# power_supply.net
KiCad netlist of a schematic drawn in Altium Designer
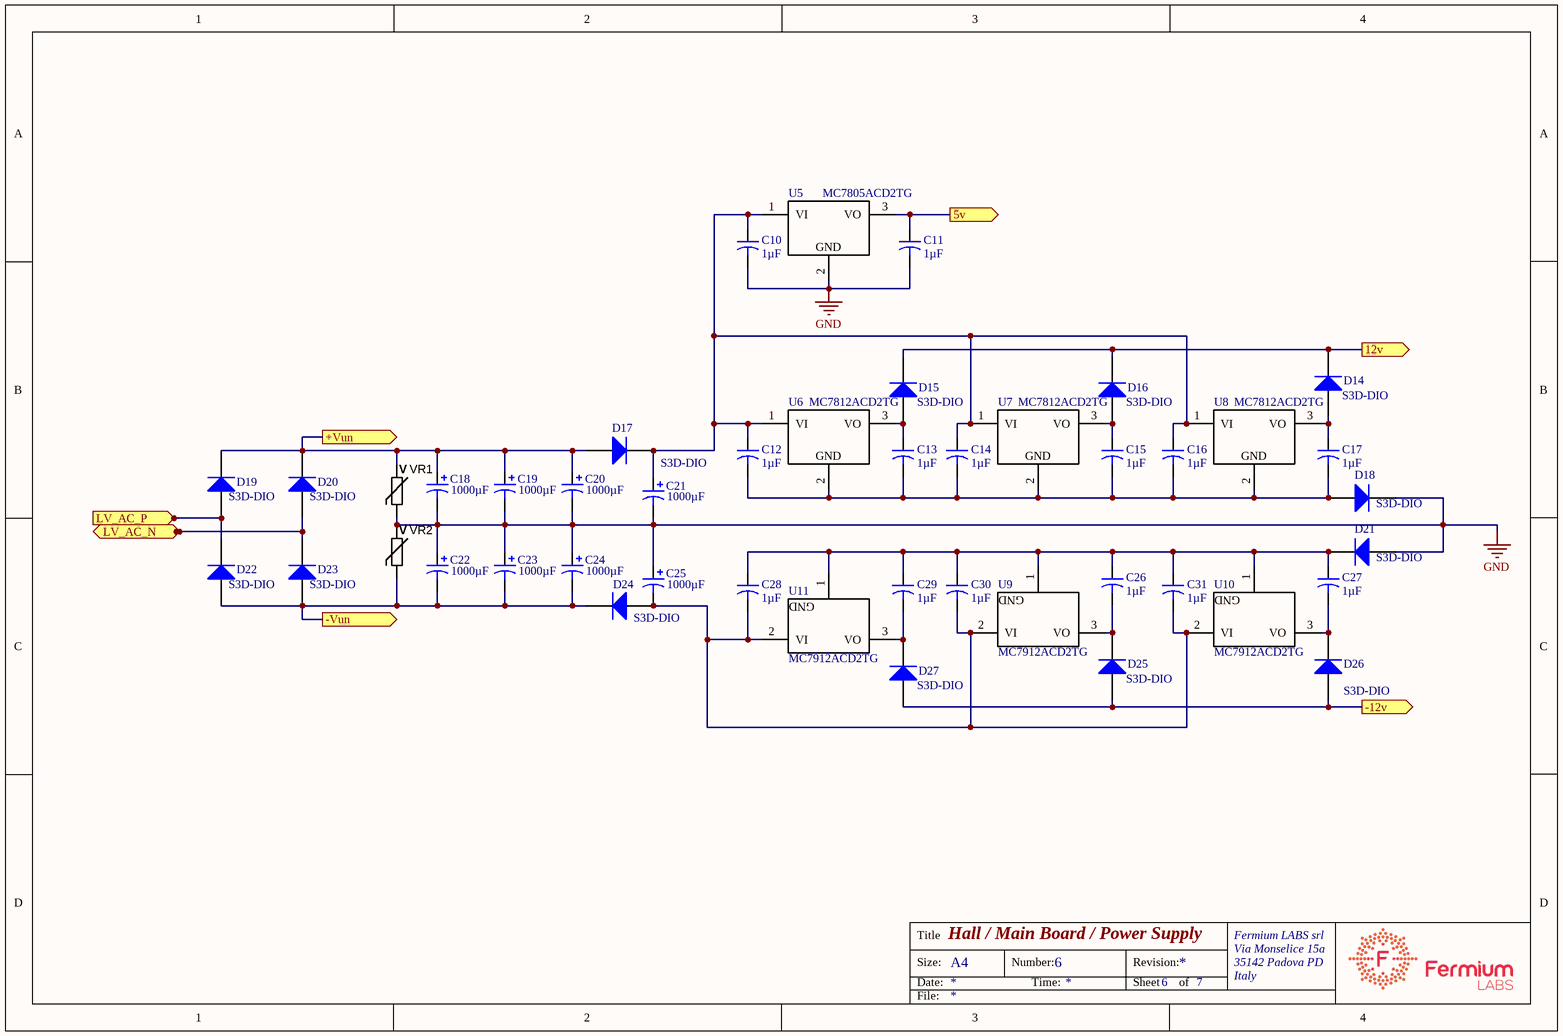
[diagram p0: power_supply.SchDoc]

(export (version "E")
  (design (tool "Eeschema 10.0.6"))
  (components
    (comp (ref "C10")
      (value "~")
      (footprint "Passives:CAP 0805/2012")
      (description "Capacitor")
      (fields
        (field (name "MANUFACTURER") "SAMSUNG")
        (field (name "MANUFACTURER PART NUMBER") "CL21B105KAFNNNE")
        (field (name "CAPACITANCE") "1µF")
        (field (name "PUBLISHER") "Altium Limited")
      )
      (libsource (lib "Miscellaneous Devices") (part "Cap2"))
    )
    (comp (ref "C11")
      (value "~")
      (footprint "Passives:CAP 0805/2012")
      (description "Capacitor")
      (fields
        (field (name "MANUFACTURER") "SAMSUNG")
        (field (name "MANUFACTURER PART NUMBER") "CL21B105KAFNNNE")
        (field (name "CAPACITANCE") "1µF")
        (field (name "PUBLISHER") "Altium Limited")
      )
      (libsource (lib "Miscellaneous Devices") (part "Cap2"))
    )
    (comp (ref "C12")
      (value "~")
      (footprint "Passives:CAP 0805/2012")
      (description "Capacitor")
      (fields
        (field (name "MANUFACTURER") "SAMSUNG")
        (field (name "MANUFACTURER PART NUMBER") "CL21B105KAFNNNE")
        (field (name "CAPACITANCE") "1µF")
        (field (name "PUBLISHER") "Altium Limited")
      )
      (libsource (lib "Miscellaneous Devices") (part "Cap2"))
    )
    (comp (ref "C13")
      (value "~")
      (footprint "Passives:CAP 0805/2012")
      (description "Capacitor")
      (fields
        (field (name "MANUFACTURER") "SAMSUNG")
        (field (name "MANUFACTURER PART NUMBER") "CL21B105KAFNNNE")
        (field (name "CAPACITANCE") "1µF")
        (field (name "PUBLISHER") "Altium Limited")
      )
      (libsource (lib "Miscellaneous Devices") (part "Cap2"))
    )
    (comp (ref "C14")
      (value "~")
      (footprint "Passives:CAP 0805/2012")
      (description "Capacitor")
      (fields
        (field (name "MANUFACTURER") "SAMSUNG")
        (field (name "MANUFACTURER PART NUMBER") "CL21B105KAFNNNE")
        (field (name "CAPACITANCE") "1µF")
        (field (name "PUBLISHER") "Altium Limited")
      )
      (libsource (lib "Miscellaneous Devices") (part "Cap2"))
    )
    (comp (ref "C15")
      (value "~")
      (footprint "Passives:CAP 0805/2012")
      (description "Capacitor")
      (fields
        (field (name "MANUFACTURER") "SAMSUNG")
        (field (name "MANUFACTURER PART NUMBER") "CL21B105KAFNNNE")
        (field (name "CAPACITANCE") "1µF")
        (field (name "PUBLISHER") "Altium Limited")
      )
      (libsource (lib "Miscellaneous Devices") (part "Cap2"))
    )
    (comp (ref "C16")
      (value "~")
      (footprint "Passives:CAP 0805/2012")
      (description "Capacitor")
      (fields
        (field (name "MANUFACTURER") "SAMSUNG")
        (field (name "MANUFACTURER PART NUMBER") "CL21B105KAFNNNE")
        (field (name "CAPACITANCE") "1µF")
        (field (name "PUBLISHER") "Altium Limited")
      )
      (libsource (lib "Miscellaneous Devices") (part "Cap2"))
    )
    (comp (ref "C17")
      (value "~")
      (footprint "Passives:CAP 0805/2012")
      (description "Capacitor")
      (fields
        (field (name "MANUFACTURER") "SAMSUNG")
        (field (name "MANUFACTURER PART NUMBER") "CL21B105KAFNNNE")
        (field (name "CAPACITANCE") "1µF")
        (field (name "PUBLISHER") "Altium Limited")
      )
      (libsource (lib "Miscellaneous Devices") (part "Cap2"))
    )
    (comp (ref "C18")
      (value "~")
      (footprint "PBL - THD Packages:CAPE5.0mm")
      (description "capacitor , electrolytic")
      (fields
        (field (name "MANUFACTURER") "NICHICON")
        (field (name "MANUFACTURER PART NUMBER") "UVZ1V102MHD")
        (field (name "CAPACITANCE") "1000µF")
        (field (name "PUBLISHER") "Altium Limited")
      )
      (libsource (lib "Miscellaneous Devices") (part "Cap Pol1"))
    )
    (comp (ref "C19")
      (value "~")
      (footprint "PBL - THD Packages:CAPE5.0mm")
      (description "capacitor , electrolytic")
      (fields
        (field (name "MANUFACTURER") "NICHICON")
        (field (name "MANUFACTURER PART NUMBER") "UVZ1V102MHD")
        (field (name "CAPACITANCE") "1000µF")
        (field (name "PUBLISHER") "Altium Limited")
      )
      (libsource (lib "Miscellaneous Devices") (part "Cap Pol1"))
    )
    (comp (ref "C20")
      (value "~")
      (footprint "PBL - THD Packages:CAPE5.0mm")
      (description "capacitor , electrolytic")
      (fields
        (field (name "MANUFACTURER") "NICHICON")
        (field (name "MANUFACTURER PART NUMBER") "UVZ1V102MHD")
        (field (name "CAPACITANCE") "1000µF")
        (field (name "PUBLISHER") "Altium Limited")
      )
      (libsource (lib "Miscellaneous Devices") (part "Cap Pol1"))
    )
    (comp (ref "C21")
      (value "~")
      (footprint "PBL - THD Packages:CAPE5.0mm")
      (description "capacitor , electrolytic")
      (fields
        (field (name "MANUFACTURER") "NICHICON")
        (field (name "MANUFACTURER PART NUMBER") "UVZ1V102MHD")
        (field (name "CAPACITANCE") "1000µF")
        (field (name "PUBLISHER") "Altium Limited")
      )
      (libsource (lib "Miscellaneous Devices") (part "Cap Pol1"))
    )
    (comp (ref "C22")
      (value "~")
      (footprint "PBL - THD Packages:CAPE5.0mm")
      (description "capacitor , electrolytic")
      (fields
        (field (name "MANUFACTURER") "NICHICON")
        (field (name "MANUFACTURER PART NUMBER") "UVZ1V102MHD")
        (field (name "CAPACITANCE") "1000µF")
        (field (name "PUBLISHER") "Altium Limited")
      )
      (libsource (lib "Miscellaneous Devices") (part "Cap Pol1"))
    )
    (comp (ref "C23")
      (value "~")
      (footprint "PBL - THD Packages:CAPE5.0mm")
      (description "capacitor , electrolytic")
      (fields
        (field (name "MANUFACTURER") "NICHICON")
        (field (name "MANUFACTURER PART NUMBER") "UVZ1V102MHD")
        (field (name "CAPACITANCE") "1000µF")
        (field (name "PUBLISHER") "Altium Limited")
      )
      (libsource (lib "Miscellaneous Devices") (part "Cap Pol1"))
    )
    (comp (ref "C24")
      (value "~")
      (footprint "PBL - THD Packages:CAPE5.0mm")
      (description "capacitor , electrolytic")
      (fields
        (field (name "MANUFACTURER") "NICHICON")
        (field (name "MANUFACTURER PART NUMBER") "UVZ1V102MHD")
        (field (name "CAPACITANCE") "1000µF")
        (field (name "PUBLISHER") "Altium Limited")
      )
      (libsource (lib "Miscellaneous Devices") (part "Cap Pol1"))
    )
    (comp (ref "C25")
      (value "~")
      (footprint "PBL - THD Packages:CAPE5.0mm")
      (description "capacitor , electrolytic")
      (fields
        (field (name "MANUFACTURER") "NICHICON")
        (field (name "MANUFACTURER PART NUMBER") "UVZ1V102MHD")
        (field (name "CAPACITANCE") "1000µF")
        (field (name "PUBLISHER") "Altium Limited")
      )
      (libsource (lib "Miscellaneous Devices") (part "Cap Pol1"))
    )
    (comp (ref "C26")
      (value "~")
      (footprint "Passives:CAP 0805/2012")
      (description "Capacitor")
      (fields
        (field (name "MANUFACTURER") "SAMSUNG")
        (field (name "MANUFACTURER PART NUMBER") "CL21B105KAFNNNE")
        (field (name "CAPACITANCE") "1µF")
        (field (name "PUBLISHER") "Altium Limited")
      )
      (libsource (lib "Miscellaneous Devices") (part "Cap2"))
    )
    (comp (ref "C27")
      (value "~")
      (footprint "Passives:CAP 0805/2012")
      (description "Capacitor")
      (fields
        (field (name "MANUFACTURER") "SAMSUNG")
        (field (name "MANUFACTURER PART NUMBER") "CL21B105KAFNNNE")
        (field (name "CAPACITANCE") "1µF")
        (field (name "PUBLISHER") "Altium Limited")
      )
      (libsource (lib "Miscellaneous Devices") (part "Cap2"))
    )
    (comp (ref "C28")
      (value "~")
      (footprint "Passives:CAP 0805/2012")
      (description "Capacitor")
      (fields
        (field (name "MANUFACTURER") "SAMSUNG")
        (field (name "MANUFACTURER PART NUMBER") "CL21B105KAFNNNE")
        (field (name "CAPACITANCE") "1µF")
        (field (name "PUBLISHER") "Altium Limited")
      )
      (libsource (lib "Miscellaneous Devices") (part "Cap2"))
    )
    (comp (ref "C29")
      (value "~")
      (footprint "Passives:CAP 0805/2012")
      (description "Capacitor")
      (fields
        (field (name "MANUFACTURER") "SAMSUNG")
        (field (name "MANUFACTURER PART NUMBER") "CL21B105KAFNNNE")
        (field (name "CAPACITANCE") "1µF")
        (field (name "PUBLISHER") "Altium Limited")
      )
      (libsource (lib "Miscellaneous Devices") (part "Cap2"))
    )
    (comp (ref "C30")
      (value "~")
      (footprint "Passives:CAP 0805/2012")
      (description "Capacitor")
      (fields
        (field (name "MANUFACTURER") "SAMSUNG")
        (field (name "MANUFACTURER PART NUMBER") "CL21B105KAFNNNE")
        (field (name "CAPACITANCE") "1µF")
        (field (name "PUBLISHER") "Altium Limited")
      )
      (libsource (lib "Miscellaneous Devices") (part "Cap2"))
    )
    (comp (ref "C31")
      (value "~")
      (footprint "Passives:CAP 0805/2012")
      (description "Capacitor")
      (fields
        (field (name "MANUFACTURER") "SAMSUNG")
        (field (name "MANUFACTURER PART NUMBER") "CL21B105KAFNNNE")
        (field (name "CAPACITANCE") "1µF")
        (field (name "PUBLISHER") "Altium Limited")
      )
      (libsource (lib "Miscellaneous Devices") (part "Cap2"))
    )
    (comp (ref "D14")
      (value "~")
      (footprint "DIODE-SMC")
      (description "Diode rectifier 1A")
      (fields
        (field (name "SUPPLIER PART NUMBER 1") "S3D-DIO")
        (field (name "MANUFACTURER") "DIOTEC SEMICONDUCTOR")
        (field (name "MANUFACTURER PART NUMBER") "S3D")
      )
      (libsource (lib "Miscellaneous Devices") (part "Diode 1N4007"))
    )
    (comp (ref "D15")
      (value "~")
      (footprint "DIODE-SMC")
      (description "Diode rectifier 1A")
      (fields
        (field (name "SUPPLIER PART NUMBER 1") "S3D-DIO")
        (field (name "MANUFACTURER") "DIOTEC SEMICONDUCTOR")
        (field (name "MANUFACTURER PART NUMBER") "S3D")
      )
      (libsource (lib "Miscellaneous Devices") (part "Diode 1N4007"))
    )
    (comp (ref "D16")
      (value "~")
      (footprint "DIODE-SMC")
      (description "Diode rectifier 1A")
      (fields
        (field (name "SUPPLIER PART NUMBER 1") "S3D-DIO")
        (field (name "MANUFACTURER") "DIOTEC SEMICONDUCTOR")
        (field (name "MANUFACTURER PART NUMBER") "S3D")
      )
      (libsource (lib "Miscellaneous Devices") (part "Diode 1N4007"))
    )
    (comp (ref "D17")
      (value "~")
      (footprint "DIODE-SMC")
      (description "Diode rectifier 1A")
      (fields
        (field (name "SUPPLIER PART NUMBER 1") "S3D-DIO")
        (field (name "MANUFACTURER") "DIOTEC SEMICONDUCTOR")
        (field (name "MANUFACTURER PART NUMBER") "S3D")
      )
      (libsource (lib "Miscellaneous Devices") (part "Diode 1N4007"))
    )
    (comp (ref "D18")
      (value "~")
      (footprint "DIODE-SMC")
      (description "Diode rectifier 1A")
      (fields
        (field (name "SUPPLIER PART NUMBER 1") "S3D-DIO")
        (field (name "MANUFACTURER") "DIOTEC SEMICONDUCTOR")
        (field (name "MANUFACTURER PART NUMBER") "S3D")
      )
      (libsource (lib "Miscellaneous Devices") (part "Diode 1N4007"))
    )
    (comp (ref "D19")
      (value "~")
      (footprint "DIODE-SMC")
      (description "Diode rectifier 1A")
      (fields
        (field (name "SUPPLIER PART NUMBER 1") "S3D-DIO")
        (field (name "MANUFACTURER") "DIOTEC SEMICONDUCTOR")
        (field (name "MANUFACTURER PART NUMBER") "S3D")
      )
      (libsource (lib "Miscellaneous Devices") (part "Diode 1N4007"))
    )
    (comp (ref "D20")
      (value "~")
      (footprint "DIODE-SMC")
      (description "Diode rectifier 1A")
      (fields
        (field (name "SUPPLIER PART NUMBER 1") "S3D-DIO")
        (field (name "MANUFACTURER") "DIOTEC SEMICONDUCTOR")
        (field (name "MANUFACTURER PART NUMBER") "S3D")
      )
      (libsource (lib "Miscellaneous Devices") (part "Diode 1N4007"))
    )
    (comp (ref "D21")
      (value "~")
      (footprint "DIODE-SMC")
      (description "Diode rectifier 1A")
      (fields
        (field (name "SUPPLIER PART NUMBER 1") "S3D-DIO")
        (field (name "MANUFACTURER") "DIOTEC SEMICONDUCTOR")
        (field (name "MANUFACTURER PART NUMBER") "S3D")
      )
      (libsource (lib "Miscellaneous Devices") (part "Diode 1N4007"))
    )
    (comp (ref "D22")
      (value "~")
      (footprint "DIODE-SMC")
      (description "Diode rectifier 1A")
      (fields
        (field (name "SUPPLIER PART NUMBER 1") "S3D-DIO")
        (field (name "MANUFACTURER") "DIOTEC SEMICONDUCTOR")
        (field (name "MANUFACTURER PART NUMBER") "S3D")
      )
      (libsource (lib "Miscellaneous Devices") (part "Diode 1N4007"))
    )
    (comp (ref "D23")
      (value "~")
      (footprint "DIODE-SMC")
      (description "Diode rectifier 1A")
      (fields
        (field (name "SUPPLIER PART NUMBER 1") "S3D-DIO")
        (field (name "MANUFACTURER") "DIOTEC SEMICONDUCTOR")
        (field (name "MANUFACTURER PART NUMBER") "S3D")
      )
      (libsource (lib "Miscellaneous Devices") (part "Diode 1N4007"))
    )
    (comp (ref "D24")
      (value "~")
      (footprint "DIODE-SMC")
      (description "Diode rectifier 1A")
      (fields
        (field (name "SUPPLIER PART NUMBER 1") "S3D-DIO")
        (field (name "MANUFACTURER") "DIOTEC SEMICONDUCTOR")
        (field (name "MANUFACTURER PART NUMBER") "S3D")
      )
      (libsource (lib "Miscellaneous Devices") (part "Diode 1N4007"))
    )
    (comp (ref "D25")
      (value "~")
      (footprint "DIODE-SMC")
      (description "Diode rectifier 1A")
      (fields
        (field (name "SUPPLIER PART NUMBER 1") "S3D-DIO")
        (field (name "MANUFACTURER") "DIOTEC SEMICONDUCTOR")
        (field (name "MANUFACTURER PART NUMBER") "S3D")
      )
      (libsource (lib "Miscellaneous Devices") (part "Diode 1N4007"))
    )
    (comp (ref "D26")
      (value "~")
      (footprint "DIODE-SMC")
      (description "Diode rectifier 1A")
      (fields
        (field (name "SUPPLIER PART NUMBER 1") "S3D-DIO")
        (field (name "MANUFACTURER") "DIOTEC SEMICONDUCTOR")
        (field (name "MANUFACTURER PART NUMBER") "S3D")
      )
      (libsource (lib "Miscellaneous Devices") (part "Diode 1N4007"))
    )
    (comp (ref "D27")
      (value "~")
      (footprint "DIODE-SMC")
      (description "Diode rectifier 1A")
      (fields
        (field (name "SUPPLIER PART NUMBER 1") "S3D-DIO")
        (field (name "MANUFACTURER") "DIOTEC SEMICONDUCTOR")
        (field (name "MANUFACTURER PART NUMBER") "S3D")
      )
      (libsource (lib "Miscellaneous Devices") (part "Diode 1N4007"))
    )
    (comp (ref "U5")
      (value "~")
      (footprint "PBL - SMD Packages:D2PAK-3")
      (description "Voltage regulator, 5V")
      (fields
        (field (name "SUPPLIER PART NUMBER 1") "MC7805ACD2TG")
        (field (name "MANUFACTURER") "ON SEMICONDUCTOR")
        (field (name "MANUFACTURER PART NUMBER") "MC7805ACD2TG")
      )
      (libsource (lib "vh_altium_library") (part "L7805-TO220"))
    )
    (comp (ref "U6")
      (value "~")
      (footprint "PBL - SMD Packages:D2PAK-3")
      (description "Voltage regulator, 15V")
      (fields
        (field (name "SUPPLIER PART NUMBER 1") "MC7812ACD2TG")
        (field (name "MANUFACTURER") "ON SEMICONDUCTOR")
        (field (name "MANUFACTURER PART NUMBER") "MC7812ACD2TG")
      )
      (libsource (lib "vh_altium_library") (part "L7815-TO220"))
    )
    (comp (ref "U7")
      (value "~")
      (footprint "PBL - SMD Packages:D2PAK-3")
      (description "Voltage regulator, 15V")
      (fields
        (field (name "SUPPLIER PART NUMBER 1") "MC7812ACD2TG")
        (field (name "MANUFACTURER") "ON SEMICONDUCTOR")
        (field (name "MANUFACTURER PART NUMBER") "MC7812ACD2TG")
      )
      (libsource (lib "vh_altium_library") (part "L7815-TO220"))
    )
    (comp (ref "U8")
      (value "~")
      (footprint "PBL - SMD Packages:D2PAK-3")
      (description "Voltage regulator, 15V")
      (fields
        (field (name "SUPPLIER PART NUMBER 1") "MC7812ACD2TG")
        (field (name "MANUFACTURER") "ON SEMICONDUCTOR")
        (field (name "MANUFACTURER PART NUMBER") "MC7812ACD2TG")
      )
      (libsource (lib "vh_altium_library") (part "L7815-TO220"))
    )
    (comp (ref "U9")
      (value "~")
      (footprint "PBL - SMD Packages:D2PAK-3")
      (description "Voltage regulator-15.0V")
      (fields
        (field (name "SUPPLIER PART NUMBER 1") "MC7912ACD2TG")
        (field (name "MANUFACTURER") "ON SEMICONDUCTOR")
        (field (name "MANUFACTURER PART NUMBER") "MC7912ACD2TG")
      )
      (libsource (lib "vh_altium_library") (part "L7915-TO220"))
    )
    (comp (ref "U10")
      (value "~")
      (footprint "PBL - SMD Packages:D2PAK-3")
      (description "Voltage regulator-15.0V")
      (fields
        (field (name "SUPPLIER PART NUMBER 1") "MC7912ACD2TG")
        (field (name "MANUFACTURER") "ON SEMICONDUCTOR")
        (field (name "MANUFACTURER PART NUMBER") "MC7912ACD2TG")
      )
      (libsource (lib "vh_altium_library") (part "L7915-TO220"))
    )
    (comp (ref "U11")
      (value "~")
      (footprint "PBL - SMD Packages:D2PAK-3")
      (description "Voltage regulator-15.0V")
      (fields
        (field (name "SUPPLIER PART NUMBER 1") "MC7912ACD2TG")
        (field (name "MANUFACTURER") "ON SEMICONDUCTOR")
        (field (name "MANUFACTURER PART NUMBER") "MC7912ACD2TG")
      )
      (libsource (lib "vh_altium_library") (part "L7915-TO220"))
    )
    (comp (ref "VR1")
      (value "~")
      (footprint "CAP 1206/3216 - 1.8MM")
      (description "Varistor")
      (fields
        (field (name "MANUFACTURER") "EPCOS")
        (field (name "MANUFACTURER PART NUMBER") "B72520T0250K062")
      )
      (libsource (lib "PBL - Fuses and Protection") (part "Varistor_MOV"))
    )
    (comp (ref "VR2")
      (value "~")
      (footprint "CAP 1206/3216 - 1.8MM")
      (description "Varistor")
      (fields
        (field (name "MANUFACTURER") "EPCOS")
        (field (name "MANUFACTURER PART NUMBER") "B72520T0250K062")
      )
      (libsource (lib "PBL - Fuses and Protection") (part "Varistor_MOV"))
    )
  )
  (nets
    (net (code "1") (name "/+Vun") (class "Default")
      (node (ref "C18") (pin "1") (pinfunction "1_1") (pintype "passive"))
      (node (ref "C19") (pin "1") (pinfunction "1_1") (pintype "passive"))
      (node (ref "C20") (pin "1") (pinfunction "1_1") (pintype "passive"))
      (node (ref "D17") (pin "A") (pinfunction "A_A") (pintype "passive"))
      (node (ref "D19") (pin "K") (pinfunction "K_K") (pintype "passive"))
      (node (ref "D20") (pin "K") (pinfunction "K_K") (pintype "passive"))
      (node (ref "VR1") (pin "1") (pinfunction "1_1") (pintype "passive"))
    )
    (net (code "2") (name "/-12v") (class "Default")
      (node (ref "D25") (pin "A") (pinfunction "A_A") (pintype "passive"))
      (node (ref "D26") (pin "A") (pinfunction "A_A") (pintype "passive"))
      (node (ref "D27") (pin "A") (pinfunction "A_A") (pintype "passive"))
    )
    (net (code "3") (name "/-Vun") (class "Default")
      (node (ref "C22") (pin "2") (pinfunction "2_2") (pintype "passive"))
      (node (ref "C23") (pin "2") (pinfunction "2_2") (pintype "passive"))
      (node (ref "C24") (pin "2") (pinfunction "2_2") (pintype "passive"))
      (node (ref "D22") (pin "A") (pinfunction "A_A") (pintype "passive"))
      (node (ref "D23") (pin "A") (pinfunction "A_A") (pintype "passive"))
      (node (ref "D24") (pin "K") (pinfunction "K_K") (pintype "passive"))
      (node (ref "VR2") (pin "2") (pinfunction "2_2") (pintype "passive"))
    )
    (net (code "4") (name "/5v") (class "Default")
      (node (ref "C11") (pin "1") (pinfunction "1_1") (pintype "passive"))
      (node (ref "U5") (pin "3") (pinfunction "VO_3") (pintype "passive"))
    )
    (net (code "5") (name "/12v") (class "Default")
      (node (ref "D14") (pin "K") (pinfunction "K_K") (pintype "passive"))
      (node (ref "D15") (pin "K") (pinfunction "K_K") (pintype "passive"))
      (node (ref "D16") (pin "K") (pinfunction "K_K") (pintype "passive"))
    )
    (net (code "6") (name "/LV_AC_N") (class "Default")
      (node (ref "D20") (pin "A") (pinfunction "A_A") (pintype "passive"))
      (node (ref "D23") (pin "K") (pinfunction "K_K") (pintype "passive"))
    )
    (net (code "7") (name "/LV_AC_P") (class "Default")
      (node (ref "D19") (pin "A") (pinfunction "A_A") (pintype "passive"))
      (node (ref "D22") (pin "K") (pinfunction "K_K") (pintype "passive"))
    )
    (net (code "8") (name "GND") (class "Default")
      (node (ref "C10") (pin "2") (pinfunction "2_2") (pintype "passive"))
      (node (ref "C11") (pin "2") (pinfunction "2_2") (pintype "passive"))
      (node (ref "C18") (pin "2") (pinfunction "2_2") (pintype "passive"))
      (node (ref "C19") (pin "2") (pinfunction "2_2") (pintype "passive"))
      (node (ref "C20") (pin "2") (pinfunction "2_2") (pintype "passive"))
      (node (ref "C21") (pin "2") (pinfunction "2_2") (pintype "passive"))
      (node (ref "C22") (pin "1") (pinfunction "1_1") (pintype "passive"))
      (node (ref "C23") (pin "1") (pinfunction "1_1") (pintype "passive"))
      (node (ref "C24") (pin "1") (pinfunction "1_1") (pintype "passive"))
      (node (ref "C25") (pin "1") (pinfunction "1_1") (pintype "passive"))
      (node (ref "D18") (pin "K") (pinfunction "K_K") (pintype "passive"))
      (node (ref "D21") (pin "A") (pinfunction "A_A") (pintype "passive"))
      (node (ref "U5") (pin "2") (pintype "passive"))
      (node (ref "VR1") (pin "2") (pinfunction "2_2") (pintype "passive"))
      (node (ref "VR2") (pin "1") (pinfunction "1_1") (pintype "passive"))
    )
    (net (code "9") (name "Net-(C12-Pad2)") (class "Default")
      (node (ref "C12") (pin "2") (pinfunction "2_2") (pintype "passive"))
      (node (ref "C13") (pin "2") (pinfunction "2_2") (pintype "passive"))
      (node (ref "C14") (pin "2") (pinfunction "2_2") (pintype "passive"))
      (node (ref "C15") (pin "2") (pinfunction "2_2") (pintype "passive"))
      (node (ref "C16") (pin "2") (pinfunction "2_2") (pintype "passive"))
      (node (ref "C17") (pin "2") (pinfunction "2_2") (pintype "passive"))
      (node (ref "D18") (pin "A") (pinfunction "A_A") (pintype "passive"))
      (node (ref "U6") (pin "2") (pintype "passive"))
      (node (ref "U7") (pin "2") (pintype "passive"))
      (node (ref "U8") (pin "2") (pintype "passive"))
    )
    (net (code "10") (name "Net-(C26-Pad1)") (class "Default")
      (node (ref "C26") (pin "1") (pinfunction "1_1") (pintype "passive"))
      (node (ref "C27") (pin "1") (pinfunction "1_1") (pintype "passive"))
      (node (ref "C28") (pin "1") (pinfunction "1_1") (pintype "passive"))
      (node (ref "C29") (pin "1") (pinfunction "1_1") (pintype "passive"))
      (node (ref "C30") (pin "1") (pinfunction "1_1") (pintype "passive"))
      (node (ref "C31") (pin "1") (pinfunction "1_1") (pintype "passive"))
      (node (ref "D21") (pin "K") (pinfunction "K_K") (pintype "passive"))
      (node (ref "U10") (pin "1") (pintype "passive"))
      (node (ref "U11") (pin "1") (pintype "passive"))
      (node (ref "U9") (pin "1") (pintype "passive"))
    )
    (net (code "11") (name "Net-(U5-VI)") (class "Default")
      (node (ref "C10") (pin "1") (pinfunction "1_1") (pintype "passive"))
      (node (ref "C12") (pin "1") (pinfunction "1_1") (pintype "passive"))
      (node (ref "C14") (pin "1") (pinfunction "1_1") (pintype "passive"))
      (node (ref "C16") (pin "1") (pinfunction "1_1") (pintype "passive"))
      (node (ref "C21") (pin "1") (pinfunction "1_1") (pintype "passive"))
      (node (ref "D17") (pin "K") (pinfunction "K_K") (pintype "passive"))
      (node (ref "U5") (pin "1") (pinfunction "VI_1") (pintype "passive"))
      (node (ref "U6") (pin "1") (pinfunction "VI_1") (pintype "passive"))
      (node (ref "U7") (pin "1") (pinfunction "VI_1") (pintype "passive"))
      (node (ref "U8") (pin "1") (pinfunction "VI_1") (pintype "passive"))
    )
    (net (code "12") (name "Net-(U6-VO)") (class "Default")
      (node (ref "C13") (pin "1") (pinfunction "1_1") (pintype "passive"))
      (node (ref "D15") (pin "A") (pinfunction "A_A") (pintype "passive"))
      (node (ref "U6") (pin "3") (pinfunction "VO_3") (pintype "passive"))
    )
    (net (code "13") (name "Net-(U7-VO)") (class "Default")
      (node (ref "C15") (pin "1") (pinfunction "1_1") (pintype "passive"))
      (node (ref "D16") (pin "A") (pinfunction "A_A") (pintype "passive"))
      (node (ref "U7") (pin "3") (pinfunction "VO_3") (pintype "passive"))
    )
    (net (code "14") (name "Net-(U8-VO)") (class "Default")
      (node (ref "C17") (pin "1") (pinfunction "1_1") (pintype "passive"))
      (node (ref "D14") (pin "A") (pinfunction "A_A") (pintype "passive"))
      (node (ref "U8") (pin "3") (pinfunction "VO_3") (pintype "passive"))
    )
    (net (code "15") (name "Net-(U9-VO)") (class "Default")
      (node (ref "C26") (pin "2") (pinfunction "2_2") (pintype "passive"))
      (node (ref "D25") (pin "K") (pinfunction "K_K") (pintype "passive"))
      (node (ref "U9") (pin "3") (pinfunction "VO_3") (pintype "passive"))
    )
    (net (code "16") (name "Net-(U10-VI)") (class "Default")
      (node (ref "C25") (pin "2") (pinfunction "2_2") (pintype "passive"))
      (node (ref "C28") (pin "2") (pinfunction "2_2") (pintype "passive"))
      (node (ref "C30") (pin "2") (pinfunction "2_2") (pintype "passive"))
      (node (ref "C31") (pin "2") (pinfunction "2_2") (pintype "passive"))
      (node (ref "D24") (pin "A") (pinfunction "A_A") (pintype "passive"))
      (node (ref "U10") (pin "2") (pinfunction "VI_2") (pintype "passive"))
      (node (ref "U11") (pin "2") (pinfunction "VI_2") (pintype "passive"))
      (node (ref "U9") (pin "2") (pinfunction "VI_2") (pintype "passive"))
    )
    (net (code "17") (name "Net-(U10-VO)") (class "Default")
      (node (ref "C27") (pin "2") (pinfunction "2_2") (pintype "passive"))
      (node (ref "D26") (pin "K") (pinfunction "K_K") (pintype "passive"))
      (node (ref "U10") (pin "3") (pinfunction "VO_3") (pintype "passive"))
    )
    (net (code "18") (name "Net-(U11-VO)") (class "Default")
      (node (ref "C29") (pin "2") (pinfunction "2_2") (pintype "passive"))
      (node (ref "D27") (pin "K") (pinfunction "K_K") (pintype "passive"))
      (node (ref "U11") (pin "3") (pinfunction "VO_3") (pintype "passive"))
    )
  )
)
